# shutdown_circuit.net
KiCad netlist of a schematic drawn in Altium Designer
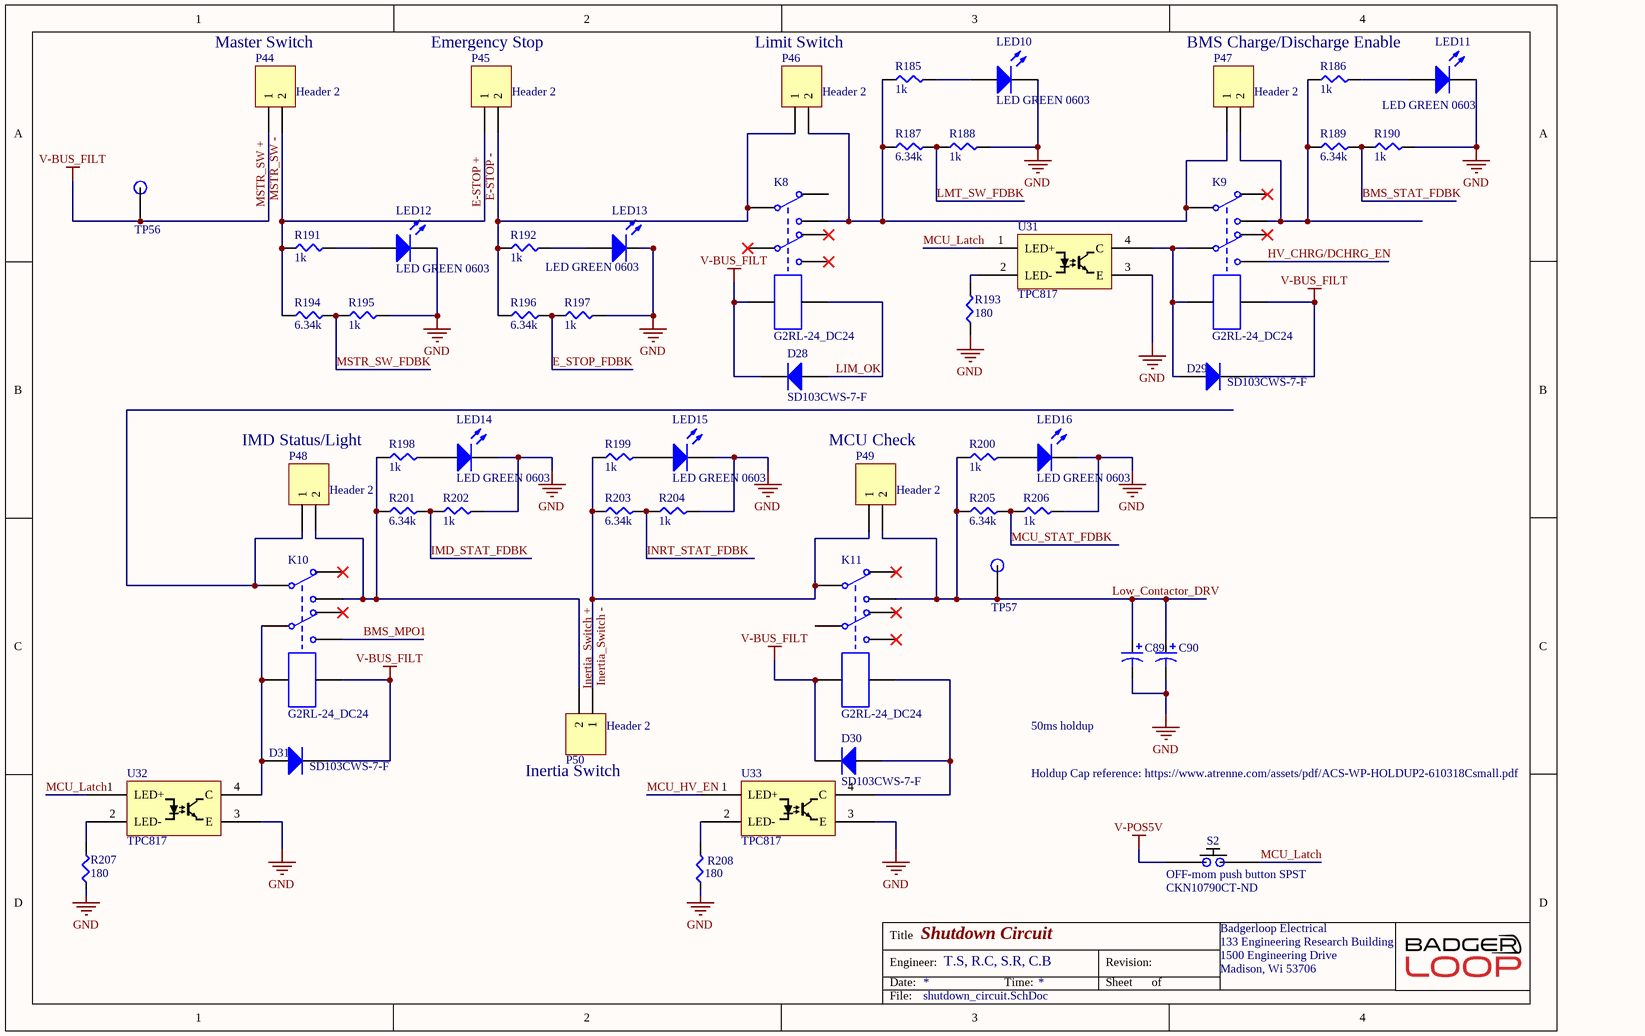
[diagram p0: shutdown_circuit.SchDoc]

(export (version "E")
  (design (tool "Eeschema 10.0.6"))
  (components
    (comp (ref "C89")
      (value "PCR1J101MCL1GS")
      (footprint "CAPAE110103X126M")
      (description "CAP ALUM POLY 100UF 20% 63V SMD")
      (fields (field (name "MANUFACTURER") "Nichicon") (field (name "TOLERANCE") "20%"))
      (libsource (lib "capacitors") (part "PCR1J101MCL1GS"))
    )
    (comp (ref "C90")
      (value "PCR1J101MCL1GS")
      (footprint "CAPAE110103X126M")
      (description "CAP ALUM POLY 100UF 20% 63V SMD")
      (fields (field (name "MANUFACTURER") "Nichicon") (field (name "TOLERANCE") "20%"))
      (libsource (lib "capacitors") (part "PCR1J101MCL1GS"))
    )
    (comp (ref "D28")
      (value "Diode General Purpose_2")
      (footprint "SODFL250X110-2N")
      (description "DIODE GEN PURP 20V 350MA SOD323")
      (fields
        (field (name "MANUFACTURER") "Diodes Incorporated")
        (field (name "MANUFACTURER P/N") "SD103CWS-7-F")
      )
      (libsource (lib "misc") (part "Diode General Purpose_2"))
    )
    (comp (ref "D29")
      (value "Diode General Purpose_2")
      (footprint "SODFL250X110-2N")
      (description "DIODE GEN PURP 20V 350MA SOD323")
      (fields
        (field (name "MANUFACTURER") "Diodes Incorporated")
        (field (name "MANUFACTURER P/N") "SD103CWS-7-F")
      )
      (libsource (lib "misc") (part "Diode General Purpose_2"))
    )
    (comp (ref "D30")
      (value "Diode General Purpose_2")
      (footprint "SODFL250X110-2N")
      (description "DIODE GEN PURP 20V 350MA SOD323")
      (fields
        (field (name "MANUFACTURER") "Diodes Incorporated")
        (field (name "MANUFACTURER P/N") "SD103CWS-7-F")
      )
      (libsource (lib "misc") (part "Diode General Purpose_2"))
    )
    (comp (ref "D31")
      (value "Diode General Purpose_2")
      (footprint "SODFL250X110-2N")
      (description "DIODE GEN PURP 20V 350MA SOD323")
      (fields
        (field (name "MANUFACTURER") "Diodes Incorporated")
        (field (name "MANUFACTURER P/N") "SD103CWS-7-F")
      )
      (libsource (lib "misc") (part "Diode General Purpose_2"))
    )
    (comp (ref "K8")
      (value "G2RL-24_DC24")
      (footprint "G2RL")
      (description "RELAY GEN PURPOSE DPDT 8A 24V")
      (fields (field (name "MANUFACTURER") "Omron") (field (name "MANUFACTURER PART NUMBER") "G2RL-24-DC24"))
      (libsource (lib "misc") (part "G2RL-24_DC24"))
    )
    (comp (ref "K9")
      (value "G2RL-24_DC24")
      (footprint "G2RL")
      (description "RELAY GEN PURPOSE DPDT 8A 24V")
      (fields (field (name "MANUFACTURER") "Omron") (field (name "MANUFACTURER PART NUMBER") "G2RL-24-DC24"))
      (libsource (lib "misc") (part "G2RL-24_DC24"))
    )
    (comp (ref "K10")
      (value "G2RL-24_DC24")
      (footprint "G2RL")
      (description "RELAY GEN PURPOSE DPDT 8A 24V")
      (fields (field (name "MANUFACTURER") "Omron") (field (name "MANUFACTURER PART NUMBER") "G2RL-24-DC24"))
      (libsource (lib "misc") (part "G2RL-24_DC24"))
    )
    (comp (ref "K11")
      (value "G2RL-24_DC24")
      (footprint "G2RL")
      (description "RELAY GEN PURPOSE DPDT 8A 24V")
      (fields (field (name "MANUFACTURER") "Omron") (field (name "MANUFACTURER PART NUMBER") "G2RL-24-DC24"))
      (libsource (lib "misc") (part "G2RL-24_DC24"))
    )
    (comp (ref "LED10")
      (value "LED GREEN 0603")
      (footprint "LED 0603 GREEN")
      (fields (field (name "MANUFACTURER") "Lite-On Inc."))
      (libsource (lib "misc") (part "LED GREEN 0603"))
    )
    (comp (ref "LED11")
      (value "LED GREEN 0603")
      (footprint "LED 0603 GREEN")
      (fields (field (name "MANUFACTURER") "Lite-On Inc."))
      (libsource (lib "misc") (part "LED GREEN 0603"))
    )
    (comp (ref "LED12")
      (value "LED GREEN 0603")
      (footprint "LED 0603 GREEN")
      (fields (field (name "MANUFACTURER") "Lite-On Inc."))
      (libsource (lib "misc") (part "LED GREEN 0603"))
    )
    (comp (ref "LED13")
      (value "LED GREEN 0603")
      (footprint "LED 0603 GREEN")
      (fields (field (name "MANUFACTURER") "Lite-On Inc."))
      (libsource (lib "misc") (part "LED GREEN 0603"))
    )
    (comp (ref "LED14")
      (value "LED GREEN 0603")
      (footprint "LED 0603 GREEN")
      (fields (field (name "MANUFACTURER") "Lite-On Inc."))
      (libsource (lib "misc") (part "LED GREEN 0603"))
    )
    (comp (ref "LED15")
      (value "LED GREEN 0603")
      (footprint "LED 0603 GREEN")
      (fields (field (name "MANUFACTURER") "Lite-On Inc."))
      (libsource (lib "misc") (part "LED GREEN 0603"))
    )
    (comp (ref "LED16")
      (value "LED GREEN 0603")
      (footprint "LED 0603 GREEN")
      (fields (field (name "MANUFACTURER") "Lite-On Inc."))
      (libsource (lib "misc") (part "LED GREEN 0603"))
    )
    (comp (ref "P44")
      (value "Header 2")
      (footprint "Pin Header 1x2 TH Pitch 2.54mm")
      (description "Header, 2-Pin")
      (fields (field (name "PUBLISHER") "Altium Limited"))
      (libsource (lib "connector") (part "Header 2"))
    )
    (comp (ref "P45")
      (value "Header 2")
      (footprint "Pin Header 1x2 TH Pitch 2.54mm")
      (description "Header, 2-Pin")
      (fields (field (name "PUBLISHER") "Altium Limited"))
      (libsource (lib "connector") (part "Header 2"))
    )
    (comp (ref "P46")
      (value "Header 2")
      (footprint "Pin Header 1x2 TH Pitch 2.54mm")
      (description "Header, 2-Pin")
      (fields (field (name "PUBLISHER") "Altium Limited"))
      (libsource (lib "connector") (part "Header 2"))
    )
    (comp (ref "P47")
      (value "Header 2")
      (footprint "Pin Header 1x2 TH Pitch 2.54mm")
      (description "Header, 2-Pin")
      (fields (field (name "PUBLISHER") "Altium Limited"))
      (libsource (lib "connector") (part "Header 2"))
    )
    (comp (ref "P48")
      (value "Header 2")
      (footprint "Pin Header 1x2 TH Pitch 2.54mm")
      (description "Header, 2-Pin")
      (fields (field (name "PUBLISHER") "Altium Limited"))
      (libsource (lib "connector") (part "Header 2"))
    )
    (comp (ref "P49")
      (value "Header 2")
      (footprint "Pin Header 1x2 TH Pitch 2.54mm")
      (description "Header, 2-Pin")
      (fields (field (name "PUBLISHER") "Altium Limited"))
      (libsource (lib "connector") (part "Header 2"))
    )
    (comp (ref "P50")
      (value "Header 2")
      (footprint "Pin Header 1x2 TH Pitch 2.54mm")
      (description "Header, 2-Pin")
      (fields (field (name "PUBLISHER") "Altium Limited"))
      (libsource (lib "") (part "Header 2_1"))
    )
    (comp (ref "R185")
      (value "1k")
      (footprint "SMD-0805-RES")
      (description "RES SMD 1K OHM 1% 1/2W 0805")
      (fields
        (field (name "PART NUMBER") "ERJ-P06F1001V")
        (field (name "DIGI-KEY PART NUMBER") "P16058CT-ND")
      )
      (libsource (lib "resistors") (part "ERJ-P06F1001V"))
    )
    (comp (ref "R186")
      (value "1k")
      (footprint "SMD-0805-RES")
      (description "RES SMD 1K OHM 1% 1/2W 0805")
      (fields
        (field (name "PART NUMBER") "ERJ-P06F1001V")
        (field (name "DIGI-KEY PART NUMBER") "P16058CT-ND")
      )
      (libsource (lib "resistors") (part "ERJ-P06F1001V"))
    )
    (comp (ref "R187")
      (value "6.34k")
      (footprint "SMD-0805-RES")
      (description "RES SMD 6.34K OHM 1% 1/8W 0805")
      (fields
        (field (name "PART NUMBER") "ERJ-6ENF6341V")
        (field (name "DIGI-KEY PART NUMBER") "P6.34KCCT-ND")
      )
      (libsource (lib "resistors") (part "ERJ-6ENF6341V"))
    )
    (comp (ref "R188")
      (value "1k")
      (footprint "SMD-0805-RES")
      (description "RES SMD 1K OHM 1% 1/2W 0805")
      (fields
        (field (name "PART NUMBER") "ERJ-P06F1001V")
        (field (name "DIGI-KEY PART NUMBER") "P16058CT-ND")
      )
      (libsource (lib "resistors") (part "ERJ-P06F1001V"))
    )
    (comp (ref "R189")
      (value "6.34k")
      (footprint "SMD-0805-RES")
      (description "RES SMD 6.34K OHM 1% 1/8W 0805")
      (fields
        (field (name "PART NUMBER") "ERJ-6ENF6341V")
        (field (name "DIGI-KEY PART NUMBER") "P6.34KCCT-ND")
      )
      (libsource (lib "resistors") (part "ERJ-6ENF6341V"))
    )
    (comp (ref "R190")
      (value "1k")
      (footprint "SMD-0805-RES")
      (description "RES SMD 1K OHM 1% 1/2W 0805")
      (fields
        (field (name "PART NUMBER") "ERJ-P06F1001V")
        (field (name "DIGI-KEY PART NUMBER") "P16058CT-ND")
      )
      (libsource (lib "resistors") (part "ERJ-P06F1001V"))
    )
    (comp (ref "R191")
      (value "1k")
      (footprint "SMD-0805-RES")
      (description "RES SMD 1K OHM 1% 1/2W 0805")
      (fields
        (field (name "PART NUMBER") "ERJ-P06F1001V")
        (field (name "DIGI-KEY PART NUMBER") "P16058CT-ND")
      )
      (libsource (lib "resistors") (part "ERJ-P06F1001V"))
    )
    (comp (ref "R192")
      (value "1k")
      (footprint "SMD-0805-RES")
      (description "RES SMD 1K OHM 1% 1/2W 0805")
      (fields
        (field (name "PART NUMBER") "ERJ-P06F1001V")
        (field (name "DIGI-KEY PART NUMBER") "P16058CT-ND")
      )
      (libsource (lib "resistors") (part "ERJ-P06F1001V"))
    )
    (comp (ref "R193")
      (value "180")
      (footprint "SMD-0805-RES")
      (description "RES SMD 180 OHM 1% 1/8W 0805")
      (fields (field (name "PART NUMBER") "ERJ-6ENF1800V") (field (name "DIGI-KEY PART NUMBER") "P180CCT-ND"))
      (libsource (lib "resistors") (part "ERJ-6ENF1800V"))
    )
    (comp (ref "R194")
      (value "6.34k")
      (footprint "SMD-0805-RES")
      (description "RES SMD 6.34K OHM 1% 1/8W 0805")
      (fields
        (field (name "PART NUMBER") "ERJ-6ENF6341V")
        (field (name "DIGI-KEY PART NUMBER") "P6.34KCCT-ND")
      )
      (libsource (lib "resistors") (part "ERJ-6ENF6341V"))
    )
    (comp (ref "R195")
      (value "1k")
      (footprint "SMD-0805-RES")
      (description "RES SMD 1K OHM 1% 1/2W 0805")
      (fields
        (field (name "PART NUMBER") "ERJ-P06F1001V")
        (field (name "DIGI-KEY PART NUMBER") "P16058CT-ND")
      )
      (libsource (lib "resistors") (part "ERJ-P06F1001V"))
    )
    (comp (ref "R196")
      (value "6.34k")
      (footprint "SMD-0805-RES")
      (description "RES SMD 6.34K OHM 1% 1/8W 0805")
      (fields
        (field (name "PART NUMBER") "ERJ-6ENF6341V")
        (field (name "DIGI-KEY PART NUMBER") "P6.34KCCT-ND")
      )
      (libsource (lib "resistors") (part "ERJ-6ENF6341V"))
    )
    (comp (ref "R197")
      (value "1k")
      (footprint "SMD-0805-RES")
      (description "RES SMD 1K OHM 1% 1/2W 0805")
      (fields
        (field (name "PART NUMBER") "ERJ-P06F1001V")
        (field (name "DIGI-KEY PART NUMBER") "P16058CT-ND")
      )
      (libsource (lib "resistors") (part "ERJ-P06F1001V"))
    )
    (comp (ref "R198")
      (value "1k")
      (footprint "SMD-0805-RES")
      (description "RES SMD 1K OHM 1% 1/2W 0805")
      (fields
        (field (name "PART NUMBER") "ERJ-P06F1001V")
        (field (name "DIGI-KEY PART NUMBER") "P16058CT-ND")
      )
      (libsource (lib "resistors") (part "ERJ-P06F1001V"))
    )
    (comp (ref "R199")
      (value "1k")
      (footprint "SMD-0805-RES")
      (description "RES SMD 1K OHM 1% 1/2W 0805")
      (fields
        (field (name "PART NUMBER") "ERJ-P06F1001V")
        (field (name "DIGI-KEY PART NUMBER") "P16058CT-ND")
      )
      (libsource (lib "resistors") (part "ERJ-P06F1001V"))
    )
    (comp (ref "R200")
      (value "1k")
      (footprint "SMD-0805-RES")
      (description "RES SMD 1K OHM 1% 1/2W 0805")
      (fields
        (field (name "PART NUMBER") "ERJ-P06F1001V")
        (field (name "DIGI-KEY PART NUMBER") "P16058CT-ND")
      )
      (libsource (lib "resistors") (part "ERJ-P06F1001V"))
    )
    (comp (ref "R201")
      (value "6.34k")
      (footprint "SMD-0805-RES")
      (description "RES SMD 6.34K OHM 1% 1/8W 0805")
      (fields
        (field (name "PART NUMBER") "ERJ-6ENF6341V")
        (field (name "DIGI-KEY PART NUMBER") "P6.34KCCT-ND")
      )
      (libsource (lib "resistors") (part "ERJ-6ENF6341V"))
    )
    (comp (ref "R202")
      (value "1k")
      (footprint "SMD-0805-RES")
      (description "RES SMD 1K OHM 1% 1/2W 0805")
      (fields
        (field (name "PART NUMBER") "ERJ-P06F1001V")
        (field (name "DIGI-KEY PART NUMBER") "P16058CT-ND")
      )
      (libsource (lib "resistors") (part "ERJ-P06F1001V"))
    )
    (comp (ref "R203")
      (value "6.34k")
      (footprint "SMD-0805-RES")
      (description "RES SMD 6.34K OHM 1% 1/8W 0805")
      (fields
        (field (name "PART NUMBER") "ERJ-6ENF6341V")
        (field (name "DIGI-KEY PART NUMBER") "P6.34KCCT-ND")
      )
      (libsource (lib "resistors") (part "ERJ-6ENF6341V"))
    )
    (comp (ref "R204")
      (value "1k")
      (footprint "SMD-0805-RES")
      (description "RES SMD 1K OHM 1% 1/2W 0805")
      (fields
        (field (name "PART NUMBER") "ERJ-P06F1001V")
        (field (name "DIGI-KEY PART NUMBER") "P16058CT-ND")
      )
      (libsource (lib "resistors") (part "ERJ-P06F1001V"))
    )
    (comp (ref "R205")
      (value "6.34k")
      (footprint "SMD-0805-RES")
      (description "RES SMD 6.34K OHM 1% 1/8W 0805")
      (fields
        (field (name "PART NUMBER") "ERJ-6ENF6341V")
        (field (name "DIGI-KEY PART NUMBER") "P6.34KCCT-ND")
      )
      (libsource (lib "resistors") (part "ERJ-6ENF6341V"))
    )
    (comp (ref "R206")
      (value "1k")
      (footprint "SMD-0805-RES")
      (description "RES SMD 1K OHM 1% 1/2W 0805")
      (fields
        (field (name "PART NUMBER") "ERJ-P06F1001V")
        (field (name "DIGI-KEY PART NUMBER") "P16058CT-ND")
      )
      (libsource (lib "resistors") (part "ERJ-P06F1001V"))
    )
    (comp (ref "R207")
      (value "180")
      (footprint "SMD-0805-RES")
      (description "RES SMD 180 OHM 1% 1/8W 0805")
      (fields (field (name "PART NUMBER") "ERJ-6ENF1800V") (field (name "DIGI-KEY PART NUMBER") "P180CCT-ND"))
      (libsource (lib "resistors") (part "ERJ-6ENF1800V"))
    )
    (comp (ref "R208")
      (value "180")
      (footprint "SMD-0805-RES")
      (description "RES SMD 180 OHM 1% 1/8W 0805")
      (fields (field (name "PART NUMBER") "ERJ-6ENF1800V") (field (name "DIGI-KEY PART NUMBER") "P180CCT-ND"))
      (libsource (lib "resistors") (part "ERJ-6ENF1800V"))
    )
    (comp (ref "S2")
      (value "OFF-mom push button SPST")
      (footprint "K12SCS1.55NOLFTX")
      (description "OFF-mom push button SPST K12SCS1.55NOLFTX")
      (fields
        (field (name "MANUFACTURER") "ITT C&K")
        (field (name "MANUFACTURER PART NUMBER") "K12SCS1.55NOLFTX")
        (field (name "SUPPLIER PART NUMBER 1") "CKN10790CT-ND")
      )
      (libsource (lib "*") (part "K12SCS1.55NOLFTX"))
    )
    (comp (ref "TP56")
      (value "TP")
      (footprint "Test Point")
      (description "SMD TEST POINT")
      (libsource (lib "misc") (part "TP"))
    )
    (comp (ref "TP57")
      (value "TP")
      (footprint "Test Point")
      (description "SMD TEST POINT")
      (libsource (lib "misc") (part "TP"))
    )
    (comp (ref "U31")
      (value "TPC817")
      (footprint "SOT200P1005X328-5N")
      (description "OPTOISO 5KV TRANS 4SOP")
      (fields (field (name "MANUFACTURER") "Taiwan Semi"))
      (libsource (lib "ic") (part "TPC817"))
    )
    (comp (ref "U32")
      (value "TPC817")
      (footprint "SOT200P1005X328-5N")
      (description "OPTOISO 5KV TRANS 4SOP")
      (fields (field (name "MANUFACTURER") "Taiwan Semi"))
      (libsource (lib "ic") (part "TPC817"))
    )
    (comp (ref "U33")
      (value "TPC817")
      (footprint "SOT200P1005X328-5N")
      (description "OPTOISO 5KV TRANS 4SOP")
      (fields (field (name "MANUFACTURER") "Taiwan Semi"))
      (libsource (lib "ic") (part "TPC817"))
    )
  )
  (nets
    (net (code "1") (name "/BMS_MPO1") (class "Default")
      (node (ref "K10") (pin "7") (pinfunction "7_7") (pintype "passive"))
    )
    (net (code "2") (name "/BMS_STAT_FDBK") (class "Default")
      (node (ref "R189") (pin "2") (pinfunction "2_2") (pintype "passive"))
      (node (ref "R190") (pin "1") (pinfunction "1_1") (pintype "passive"))
    )
    (net (code "3") (name "/E-STOP +") (class "Default")
      (node (ref "P44") (pin "2") (pinfunction "2_2") (pintype "passive"))
      (node (ref "P45") (pin "1") (pinfunction "1_1") (pintype "passive"))
      (node (ref "R191") (pin "1") (pinfunction "1_1") (pintype "passive"))
      (node (ref "R194") (pin "1") (pinfunction "1_1") (pintype "passive"))
    )
    (net (code "4") (name "/E-STOP -") (class "Default")
      (node (ref "K8") (pin "3") (pinfunction "3_3") (pintype "passive"))
      (node (ref "P45") (pin "2") (pinfunction "2_2") (pintype "passive"))
      (node (ref "P46") (pin "1") (pinfunction "1_1") (pintype "passive"))
      (node (ref "R192") (pin "1") (pinfunction "1_1") (pintype "passive"))
      (node (ref "R196") (pin "1") (pinfunction "1_1") (pintype "passive"))
    )
    (net (code "5") (name "/E_STOP_FDBK") (class "Default")
      (node (ref "R196") (pin "2") (pinfunction "2_2") (pintype "passive"))
      (node (ref "R197") (pin "1") (pinfunction "1_1") (pintype "passive"))
    )
    (net (code "6") (name "/HV_CHRG{slash}DCHRG_EN") (class "Default")
      (node (ref "K9") (pin "7") (pinfunction "7_7") (pintype "passive"))
    )
    (net (code "7") (name "/IMD_STAT_FDBK") (class "Default")
      (node (ref "R201") (pin "2") (pinfunction "2_2") (pintype "passive"))
      (node (ref "R202") (pin "1") (pinfunction "1_1") (pintype "passive"))
    )
    (net (code "8") (name "/INRT_STAT_FDBK") (class "Default")
      (node (ref "R203") (pin "2") (pinfunction "2_2") (pintype "passive"))
      (node (ref "R204") (pin "1") (pinfunction "1_1") (pintype "passive"))
    )
    (net (code "9") (name "/Inertia_Switch +") (class "Default")
      (node (ref "K10") (pin "4") (pinfunction "4_4") (pintype "passive"))
      (node (ref "P48") (pin "2") (pinfunction "2_2") (pintype "passive"))
      (node (ref "P50") (pin "2") (pinfunction "2_2") (pintype "passive"))
      (node (ref "R198") (pin "1") (pinfunction "1_1") (pintype "passive"))
      (node (ref "R201") (pin "1") (pinfunction "1_1") (pintype "passive"))
    )
    (net (code "10") (name "/Inertia_Switch -") (class "Default")
      (node (ref "K11") (pin "3") (pinfunction "3_3") (pintype "passive"))
      (node (ref "P49") (pin "1") (pinfunction "1_1") (pintype "passive"))
      (node (ref "P50") (pin "1") (pinfunction "1_1") (pintype "passive"))
      (node (ref "R199") (pin "1") (pinfunction "1_1") (pintype "passive"))
      (node (ref "R203") (pin "1") (pinfunction "1_1") (pintype "passive"))
    )
    (net (code "11") (name "/LIM_OK") (class "Default")
      (node (ref "D28") (pin "1") (pinfunction "A_1") (pintype "passive"))
      (node (ref "K8") (pin "8") (pinfunction "8_8") (pintype "passive"))
    )
    (net (code "12") (name "/LMT_SW_FDBK") (class "Default")
      (node (ref "R187") (pin "2") (pinfunction "2_2") (pintype "passive"))
      (node (ref "R188") (pin "1") (pinfunction "1_1") (pintype "passive"))
    )
    (net (code "13") (name "/Low_Contactor_DRV") (class "Default")
      (node (ref "C89") (pin "1") (pinfunction "1_1") (pintype "passive"))
      (node (ref "C90") (pin "1") (pinfunction "1_1") (pintype "passive"))
      (node (ref "K11") (pin "4") (pinfunction "4_4") (pintype "passive"))
      (node (ref "P49") (pin "2") (pinfunction "2_2") (pintype "passive"))
      (node (ref "R200") (pin "1") (pinfunction "1_1") (pintype "passive"))
      (node (ref "R205") (pin "1") (pinfunction "1_1") (pintype "passive"))
      (node (ref "TP57") (pin "1") (pinfunction "1_1") (pintype "passive"))
    )
    (net (code "14") (name "/MCU_HV_EN") (class "Default")
      (node (ref "U33") (pin "1") (pinfunction "LED+_1") (pintype "passive"))
    )
    (net (code "15") (name "/MCU_Latch") (class "Default")
      (node (ref "S2") (pin "2") (pinfunction "2_2") (pintype "passive"))
      (node (ref "U31") (pin "1") (pinfunction "LED+_1") (pintype "passive"))
      (node (ref "U32") (pin "1") (pinfunction "LED+_1") (pintype "passive"))
    )
    (net (code "16") (name "/MCU_STAT_FDBK") (class "Default")
      (node (ref "R205") (pin "2") (pinfunction "2_2") (pintype "passive"))
      (node (ref "R206") (pin "1") (pinfunction "1_1") (pintype "passive"))
    )
    (net (code "17") (name "/MSTR_SW_FDBK") (class "Default")
      (node (ref "R194") (pin "2") (pinfunction "2_2") (pintype "passive"))
      (node (ref "R195") (pin "1") (pinfunction "1_1") (pintype "passive"))
    )
    (net (code "18") (name "GND") (class "Default")
      (node (ref "C89") (pin "2") (pinfunction "2_2") (pintype "passive"))
      (node (ref "C90") (pin "2") (pinfunction "2_2") (pintype "passive"))
      (node (ref "LED10") (pin "2") (pinfunction "K_2") (pintype "passive"))
      (node (ref "LED11") (pin "2") (pinfunction "K_2") (pintype "passive"))
      (node (ref "LED12") (pin "2") (pinfunction "K_2") (pintype "passive"))
      (node (ref "LED13") (pin "2") (pinfunction "K_2") (pintype "passive"))
      (node (ref "LED14") (pin "2") (pinfunction "K_2") (pintype "passive"))
      (node (ref "LED15") (pin "2") (pinfunction "K_2") (pintype "passive"))
      (node (ref "LED16") (pin "2") (pinfunction "K_2") (pintype "passive"))
      (node (ref "R188") (pin "2") (pinfunction "2_2") (pintype "passive"))
      (node (ref "R190") (pin "2") (pinfunction "2_2") (pintype "passive"))
      (node (ref "R193") (pin "1") (pinfunction "1_1") (pintype "passive"))
      (node (ref "R195") (pin "2") (pinfunction "2_2") (pintype "passive"))
      (node (ref "R197") (pin "2") (pinfunction "2_2") (pintype "passive"))
      (node (ref "R202") (pin "2") (pinfunction "2_2") (pintype "passive"))
      (node (ref "R204") (pin "2") (pinfunction "2_2") (pintype "passive"))
      (node (ref "R206") (pin "2") (pinfunction "2_2") (pintype "passive"))
      (node (ref "R207") (pin "1") (pinfunction "1_1") (pintype "passive"))
      (node (ref "R208") (pin "1") (pinfunction "1_1") (pintype "passive"))
      (node (ref "U31") (pin "3") (pinfunction "E_3") (pintype "passive"))
      (node (ref "U32") (pin "3") (pinfunction "E_3") (pintype "passive"))
      (node (ref "U33") (pin "3") (pinfunction "E_3") (pintype "passive"))
    )
    (net (code "19") (name "Net-(D29-A)") (class "Default")
      (node (ref "D29") (pin "1") (pinfunction "A_1") (pintype "passive"))
      (node (ref "K9") (pin "1") (pinfunction "1_1") (pintype "passive"))
      (node (ref "K9") (pin "6") (pinfunction "6_6") (pintype "passive"))
      (node (ref "U31") (pin "4") (pinfunction "C_4") (pintype "passive"))
    )
    (net (code "20") (name "Net-(D30-A)") (class "Default")
      (node (ref "D30") (pin "1") (pinfunction "A_1") (pintype "passive"))
      (node (ref "K11") (pin "8") (pinfunction "8_8") (pintype "passive"))
      (node (ref "U33") (pin "4") (pinfunction "C_4") (pintype "passive"))
    )
    (net (code "21") (name "Net-(D31-A)") (class "Default")
      (node (ref "D31") (pin "1") (pinfunction "A_1") (pintype "passive"))
      (node (ref "K10") (pin "1") (pinfunction "1_1") (pintype "passive"))
      (node (ref "K10") (pin "6") (pinfunction "6_6") (pintype "passive"))
      (node (ref "U32") (pin "4") (pinfunction "C_4") (pintype "passive"))
    )
    (net (code "22") (name "Net-(K8-Pad4)") (class "Default")
      (node (ref "K8") (pin "4") (pinfunction "4_4") (pintype "passive"))
      (node (ref "K9") (pin "3") (pinfunction "3_3") (pintype "passive"))
      (node (ref "P46") (pin "2") (pinfunction "2_2") (pintype "passive"))
      (node (ref "P47") (pin "1") (pinfunction "1_1") (pintype "passive"))
      (node (ref "R185") (pin "1") (pinfunction "1_1") (pintype "passive"))
      (node (ref "R187") (pin "1") (pinfunction "1_1") (pintype "passive"))
    )
    (net (code "23") (name "Net-(K9-Pad4)") (class "Default")
      (node (ref "K9") (pin "4") (pinfunction "4_4") (pintype "passive"))
      (node (ref "P47") (pin "2") (pinfunction "2_2") (pintype "passive"))
      (node (ref "R186") (pin "1") (pinfunction "1_1") (pintype "passive"))
      (node (ref "R189") (pin "1") (pinfunction "1_1") (pintype "passive"))
    )
    (net (code "24") (name "Net-(K10-Pad3)") (class "Default")
      (node (ref "K10") (pin "3") (pinfunction "3_3") (pintype "passive"))
      (node (ref "P48") (pin "1") (pinfunction "1_1") (pintype "passive"))
    )
    (net (code "25") (name "Net-(LED10-A)") (class "Default")
      (node (ref "LED10") (pin "1") (pinfunction "A_1") (pintype "passive"))
      (node (ref "R185") (pin "2") (pinfunction "2_2") (pintype "passive"))
    )
    (net (code "26") (name "Net-(LED11-A)") (class "Default")
      (node (ref "LED11") (pin "1") (pinfunction "A_1") (pintype "passive"))
      (node (ref "R186") (pin "2") (pinfunction "2_2") (pintype "passive"))
    )
    (net (code "27") (name "Net-(LED12-A)") (class "Default")
      (node (ref "LED12") (pin "1") (pinfunction "A_1") (pintype "passive"))
      (node (ref "R191") (pin "2") (pinfunction "2_2") (pintype "passive"))
    )
    (net (code "28") (name "Net-(LED13-A)") (class "Default")
      (node (ref "LED13") (pin "1") (pinfunction "A_1") (pintype "passive"))
      (node (ref "R192") (pin "2") (pinfunction "2_2") (pintype "passive"))
    )
    (net (code "29") (name "Net-(LED14-A)") (class "Default")
      (node (ref "LED14") (pin "1") (pinfunction "A_1") (pintype "passive"))
      (node (ref "R198") (pin "2") (pinfunction "2_2") (pintype "passive"))
    )
    (net (code "30") (name "Net-(LED15-A)") (class "Default")
      (node (ref "LED15") (pin "1") (pinfunction "A_1") (pintype "passive"))
      (node (ref "R199") (pin "2") (pinfunction "2_2") (pintype "passive"))
    )
    (net (code "31") (name "Net-(LED16-A)") (class "Default")
      (node (ref "LED16") (pin "1") (pinfunction "A_1") (pintype "passive"))
      (node (ref "R200") (pin "2") (pinfunction "2_2") (pintype "passive"))
    )
    (net (code "32") (name "Net-(U31-LED-)") (class "Default")
      (node (ref "R193") (pin "2") (pinfunction "2_2") (pintype "passive"))
      (node (ref "U31") (pin "2") (pinfunction "LED-_2") (pintype "passive"))
    )
    (net (code "33") (name "Net-(U32-LED-)") (class "Default")
      (node (ref "R207") (pin "2") (pinfunction "2_2") (pintype "passive"))
      (node (ref "U32") (pin "2") (pinfunction "LED-_2") (pintype "passive"))
    )
    (net (code "34") (name "Net-(U33-LED-)") (class "Default")
      (node (ref "R208") (pin "2") (pinfunction "2_2") (pintype "passive"))
      (node (ref "U33") (pin "2") (pinfunction "LED-_2") (pintype "passive"))
    )
    (net (code "35") (name "V-BUS_FILT") (class "Default")
      (node (ref "D28") (pin "2") (pinfunction "K_2") (pintype "passive"))
      (node (ref "D29") (pin "2") (pinfunction "K_2") (pintype "passive"))
      (node (ref "D30") (pin "2") (pinfunction "K_2") (pintype "passive"))
      (node (ref "D31") (pin "2") (pinfunction "K_2") (pintype "passive"))
      (node (ref "K10") (pin "8") (pinfunction "8_8") (pintype "passive"))
      (node (ref "K11") (pin "1") (pinfunction "1_1") (pintype "passive"))
      (node (ref "K8") (pin "1") (pinfunction "1_1") (pintype "passive"))
      (node (ref "K9") (pin "8") (pinfunction "8_8") (pintype "passive"))
      (node (ref "P44") (pin "1") (pinfunction "1_1") (pintype "passive"))
      (node (ref "TP56") (pin "1") (pinfunction "1_1") (pintype "passive"))
    )
    (net (code "36") (name "V-POS5V") (class "Default")
      (node (ref "S2") (pin "1") (pinfunction "1_1") (pintype "passive"))
    )
    (net (code "37") (name "unconnected-(K8-Pad2)") (class "Default")
      (node (ref "K8") (pin "2") (pinfunction "2_2") (pintype "passive"))
    )
    (net (code "38") (name "unconnected-(K8-Pad5)") (class "Default")
      (node (ref "K8") (pin "5") (pinfunction "5_5") (pintype "passive+no_connect"))
    )
    (net (code "39") (name "unconnected-(K8-Pad6)") (class "Default")
      (node (ref "K8") (pin "6") (pinfunction "6_6") (pintype "passive+no_connect"))
    )
    (net (code "40") (name "unconnected-(K8-Pad7)") (class "Default")
      (node (ref "K8") (pin "7") (pinfunction "7_7") (pintype "passive+no_connect"))
    )
    (net (code "41") (name "unconnected-(K9-Pad2)") (class "Default")
      (node (ref "K9") (pin "2") (pinfunction "2_2") (pintype "passive+no_connect"))
    )
    (net (code "42") (name "unconnected-(K9-Pad5)") (class "Default")
      (node (ref "K9") (pin "5") (pinfunction "5_5") (pintype "passive+no_connect"))
    )
    (net (code "43") (name "unconnected-(K10-Pad2)") (class "Default")
      (node (ref "K10") (pin "2") (pinfunction "2_2") (pintype "passive+no_connect"))
    )
    (net (code "44") (name "unconnected-(K10-Pad5)") (class "Default")
      (node (ref "K10") (pin "5") (pinfunction "5_5") (pintype "passive+no_connect"))
    )
    (net (code "45") (name "unconnected-(K11-Pad2)") (class "Default")
      (node (ref "K11") (pin "2") (pinfunction "2_2") (pintype "passive+no_connect"))
    )
    (net (code "46") (name "unconnected-(K11-Pad5)") (class "Default")
      (node (ref "K11") (pin "5") (pinfunction "5_5") (pintype "passive+no_connect"))
    )
    (net (code "47") (name "unconnected-(K11-Pad6)") (class "Default")
      (node (ref "K11") (pin "6") (pinfunction "6_6") (pintype "passive"))
    )
    (net (code "48") (name "unconnected-(K11-Pad7)") (class "Default")
      (node (ref "K11") (pin "7") (pinfunction "7_7") (pintype "passive+no_connect"))
    )
  )
)
